# blink1mk2_v2c6.net
KiCad netlist of a schematic drawn in EAGLE
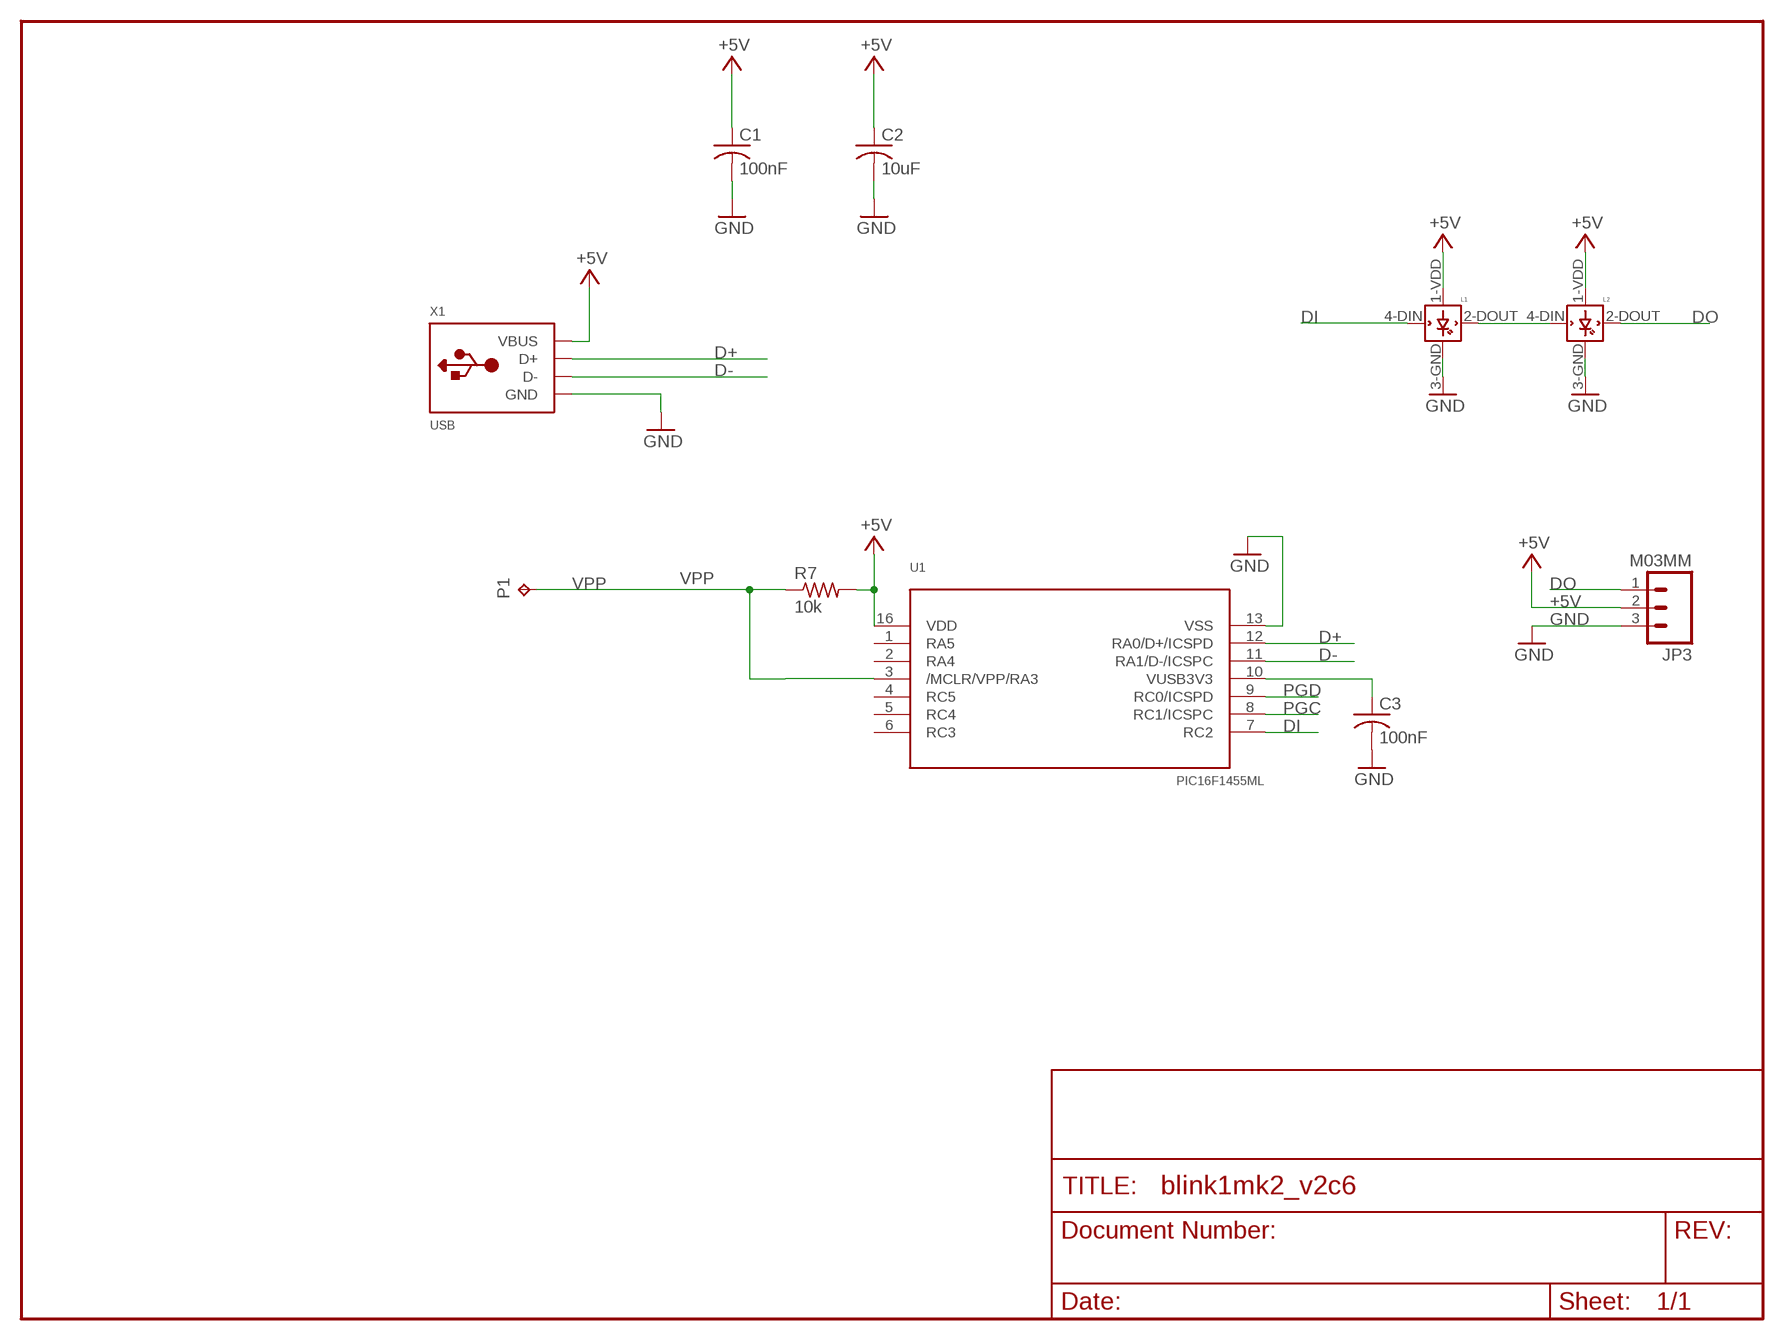
[diagram p0: schematic, sheet 1]

(export (version "E")
  (design (tool "Eeschema 10.0.6"))
  (components
    (comp (ref "C1")
      (value "100nF")
      (footprint "eagle-import:C0603")
      (libsource (lib "eagle-import") (part "C-USC0603"))
    )
    (comp (ref "C2")
      (value "10uF")
      (footprint "eagle-import:C0603")
      (libsource (lib "eagle-import") (part "C-USC0603"))
    )
    (comp (ref "C3")
      (value "100nF")
      (footprint "eagle-import:C0603")
      (libsource (lib "eagle-import") (part "C-USC0603"))
    )
    (comp (ref "JP3")
      (value "M03MM")
      (footprint "eagle-import:1X03-1.5MM")
      (libsource (lib "eagle-import") (part "M03MM"))
    )
    (comp (ref "L1")
      (value "WS2812B")
      (footprint "eagle-import:WS2812B")
      (libsource (lib "eagle-import") (part "WS2812B"))
    )
    (comp (ref "L2")
      (value "WS2812B")
      (footprint "eagle-import:WS2812B")
      (libsource (lib "eagle-import") (part "WS2812B"))
    )
    (comp (ref "P1")
      (value "TPTP11SQ")
      (footprint "eagle-import:TP11SQ")
      (libsource (lib "eagle-import") (part "TPTP11SQ"))
    )
    (comp (ref "R7")
      (value "10k")
      (footprint "eagle-import:R0603")
      (libsource (lib "eagle-import") (part "R-US_R0603"))
    )
    (comp (ref "U1")
      (value "PIC16F1455ML")
      (footprint "eagle-import:QFN16_4X4")
      (libsource (lib "eagle-import") (part "PIC16F1455ML"))
    )
    (comp (ref "X1")
      (value "USB")
      (footprint "eagle-import:MOLEX-48037-1000")
      (libsource (lib "eagle-import") (part "USB"))
    )
  )
  (nets
    (net (code "1") (name "+5V") (class "Default")
      (node (ref "C1") (pin "1") (pinfunction "1_1") (pintype "passive"))
      (node (ref "C2") (pin "1") (pinfunction "1_1") (pintype "passive"))
      (node (ref "JP3") (pin "2") (pinfunction "2_2") (pintype "passive"))
      (node (ref "L1") (pin "1-VDD") (pinfunction "VDD_1-VDD") (pintype "bidirectional"))
      (node (ref "L2") (pin "1-VDD") (pinfunction "VDD_1-VDD") (pintype "bidirectional"))
      (node (ref "R7") (pin "2") (pinfunction "2_2") (pintype "passive"))
      (node (ref "U1") (pin "16") (pinfunction "VDD_16") (pintype "bidirectional"))
      (node (ref "X1") (pin "1") (pinfunction "VBUS_1") (pintype "power_in"))
    )
    (net (code "2") (name "/D+") (class "Default")
      (node (ref "U1") (pin "12") (pinfunction "RA0/D+/ICSPD_12") (pintype "bidirectional"))
      (node (ref "X1") (pin "3") (pinfunction "D+_3") (pintype "bidirectional"))
    )
    (net (code "3") (name "/D-") (class "Default")
      (node (ref "U1") (pin "11") (pinfunction "RA1/D-/ICSPC_11") (pintype "bidirectional"))
      (node (ref "X1") (pin "2") (pinfunction "D-_2") (pintype "bidirectional"))
    )
    (net (code "4") (name "/DI") (class "Default")
      (node (ref "L1") (pin "4-DIN") (pinfunction "DIN_4-DIN") (pintype "input"))
      (node (ref "U1") (pin "7") (pinfunction "RC2_7") (pintype "bidirectional"))
    )
    (net (code "5") (name "/DO") (class "Default")
      (node (ref "JP3") (pin "1") (pinfunction "1_1") (pintype "passive"))
      (node (ref "L2") (pin "2-DOUT") (pinfunction "DOUT_2-DOUT") (pintype "output"))
    )
    (net (code "6") (name "/PGC") (class "Default")
      (node (ref "U1") (pin "8") (pinfunction "RC1/ICSPC_8") (pintype "bidirectional"))
    )
    (net (code "7") (name "/PGD") (class "Default")
      (node (ref "U1") (pin "9") (pinfunction "RC0/ICSPD_9") (pintype "bidirectional"))
    )
    (net (code "8") (name "/VPP") (class "Default")
      (node (ref "P1") (pin "TP") (pinfunction "TP_TP") (pintype "input"))
      (node (ref "R7") (pin "1") (pinfunction "1_1") (pintype "passive"))
      (node (ref "U1") (pin "3") (pinfunction "/MCLR/VPP/RA3_3") (pintype "bidirectional"))
    )
    (net (code "9") (name "GND") (class "Default")
      (node (ref "C1") (pin "2") (pinfunction "2_2") (pintype "passive"))
      (node (ref "C2") (pin "2") (pinfunction "2_2") (pintype "passive"))
      (node (ref "C3") (pin "2") (pinfunction "2_2") (pintype "passive"))
      (node (ref "JP3") (pin "3") (pinfunction "3_3") (pintype "passive"))
      (node (ref "L1") (pin "3-GND") (pinfunction "GND_3-GND") (pintype "bidirectional"))
      (node (ref "L2") (pin "3-GND") (pinfunction "GND_3-GND") (pintype "bidirectional"))
      (node (ref "U1") (pin "13") (pinfunction "VSS_13") (pintype "bidirectional"))
      (node (ref "X1") (pin "4") (pinfunction "GND_4") (pintype "power_in"))
    )
    (net (code "10") (name "Net-(L1-DOUT)") (class "Default")
      (node (ref "L1") (pin "2-DOUT") (pinfunction "DOUT_2-DOUT") (pintype "output"))
      (node (ref "L2") (pin "4-DIN") (pinfunction "DIN_4-DIN") (pintype "input"))
    )
    (net (code "11") (name "Net-(U1-VUSB3V3)") (class "Default")
      (node (ref "C3") (pin "1") (pinfunction "1_1") (pintype "passive"))
      (node (ref "U1") (pin "10") (pinfunction "VUSB3V3_10") (pintype "bidirectional"))
    )
    (net (code "12") (name "unconnected-(U1-RA4-Pad2)") (class "Default")
      (node (ref "U1") (pin "2") (pinfunction "RA4_2") (pintype "bidirectional"))
    )
    (net (code "13") (name "unconnected-(U1-RA5-Pad1)") (class "Default")
      (node (ref "U1") (pin "1") (pinfunction "RA5_1") (pintype "bidirectional"))
    )
    (net (code "14") (name "unconnected-(U1-RC3-Pad6)") (class "Default")
      (node (ref "U1") (pin "6") (pinfunction "RC3_6") (pintype "bidirectional"))
    )
    (net (code "15") (name "unconnected-(U1-RC4-Pad5)") (class "Default")
      (node (ref "U1") (pin "5") (pinfunction "RC4_5") (pintype "bidirectional"))
    )
    (net (code "16") (name "unconnected-(U1-RC5-Pad4)") (class "Default")
      (node (ref "U1") (pin "4") (pinfunction "RC5_4") (pintype "bidirectional"))
    )
  )
)
